# Stm32.net
KiCad netlist of a schematic drawn in Altium Designer
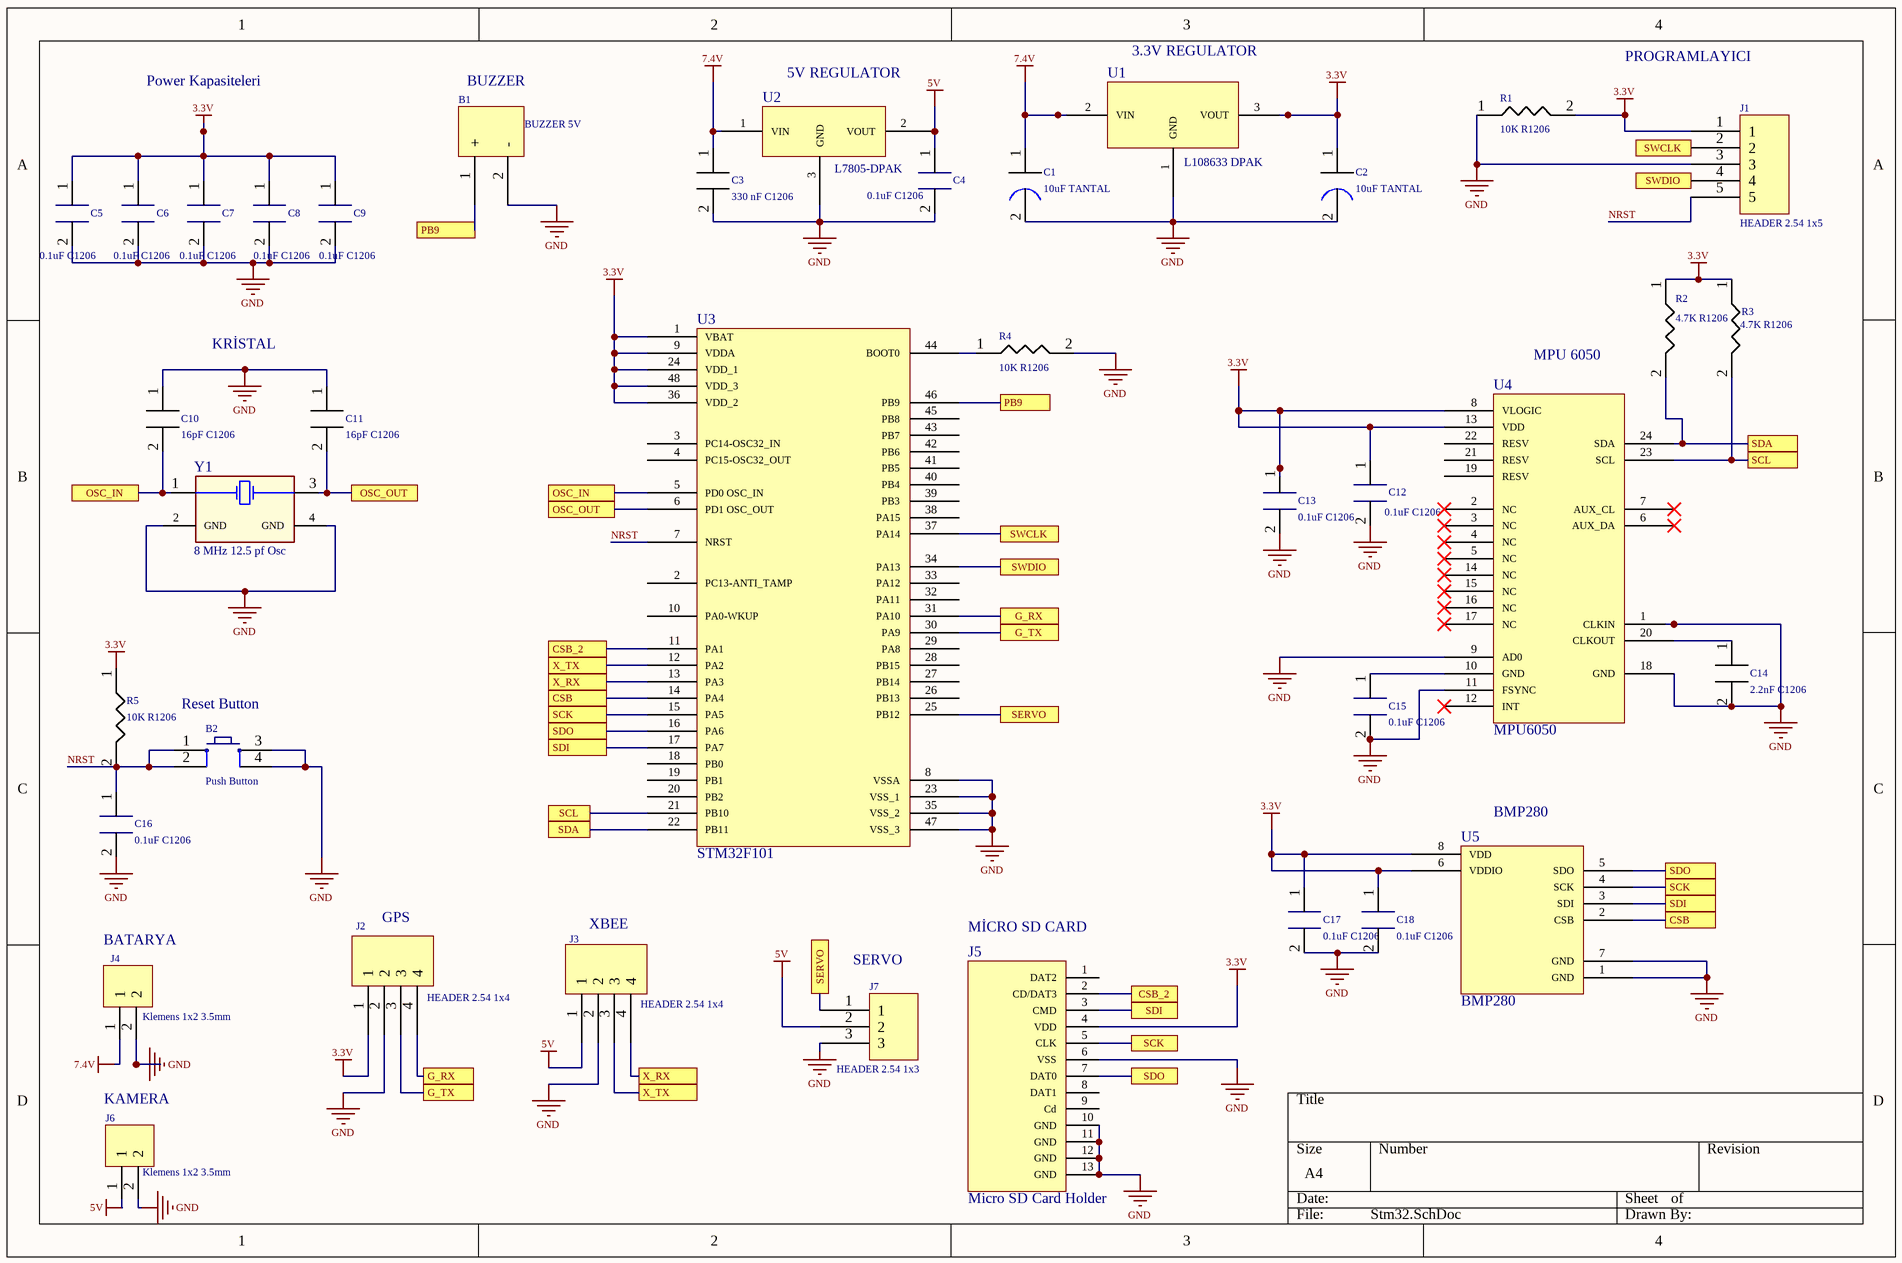
[diagram p0: Stm32.SchDoc]

(export (version "E")
  (design (tool "Eeschema 10.0.6"))
  (components
    (comp (ref "B1")
      (value "BUZZER 5V")
      (footprint "BUZZER 5V")
      (description "BUZZER 5v")
      (libsource (lib "Stm32") (part "BUZZER 5V"))
    )
    (comp (ref "B2")
      (value "Push Button")
      (footprint "PUSB BUTTON-SMD")
      (description "Smd Push Button")
      (libsource (lib "Stm32") (part "Push Button"))
    )
    (comp (ref "C1")
      (value "10uF TANTAL")
      (footprint "C1206- TANTAL")
      (libsource (lib "Stm32") (part "10uF TANTAL"))
    )
    (comp (ref "C2")
      (value "10uF TANTAL")
      (footprint "C1206- TANTAL")
      (libsource (lib "Stm32") (part "10uF TANTAL"))
    )
    (comp (ref "C3")
      (value "330 nF C1206")
      (footprint "C1206")
      (description "330nF C1206")
      (libsource (lib "Stm32") (part "330 nF C1206"))
    )
    (comp (ref "C4") (value "0.1uF C1206") (footprint "C1206") (libsource (lib "Stm32") (part "0.1uF C1206")))
    (comp (ref "C5") (value "0.1uF C1206") (footprint "C1206") (libsource (lib "Stm32") (part "0.1uF C1206")))
    (comp (ref "C6") (value "0.1uF C1206") (footprint "C1206") (libsource (lib "Stm32") (part "0.1uF C1206")))
    (comp (ref "C7") (value "0.1uF C1206") (footprint "C1206") (libsource (lib "Stm32") (part "0.1uF C1206")))
    (comp (ref "C8") (value "0.1uF C1206") (footprint "C1206") (libsource (lib "Stm32") (part "0.1uF C1206")))
    (comp (ref "C9") (value "0.1uF C1206") (footprint "C1206") (libsource (lib "Stm32") (part "0.1uF C1206")))
    (comp (ref "C10") (value "16pF C1206") (footprint "C1206") (libsource (lib "Stm32") (part "16pF C1206")))
    (comp (ref "C11") (value "16pF C1206") (footprint "C1206") (libsource (lib "Stm32") (part "16pF C1206")))
    (comp (ref "C12")
      (value "0.1uF C1206")
      (footprint "C1206")
      (libsource (lib "Stm32") (part "0.1uF C1206"))
    )
    (comp (ref "C13")
      (value "0.1uF C1206")
      (footprint "C1206")
      (libsource (lib "Stm32") (part "0.1uF C1206"))
    )
    (comp (ref "C14")
      (value "2.2nF C1206")
      (footprint "C1206")
      (description "10nF C1206")
      (libsource (lib "Stm32") (part "2.2nF C1206"))
    )
    (comp (ref "C15")
      (value "0.1uF C1206")
      (footprint "C1206")
      (libsource (lib "Stm32") (part "0.1uF C1206"))
    )
    (comp (ref "C16")
      (value "0.1uF C1206")
      (footprint "C1206")
      (libsource (lib "Stm32") (part "0.1uF C1206"))
    )
    (comp (ref "C17")
      (value "0.1uF C1206")
      (footprint "C1206")
      (libsource (lib "Stm32") (part "0.1uF C1206"))
    )
    (comp (ref "C18")
      (value "0.1uF C1206")
      (footprint "C1206")
      (libsource (lib "Stm32") (part "0.1uF C1206"))
    )
    (comp (ref "J1")
      (value "HEADER 2.54 1x5")
      (footprint "HEADER 2.54 1x5")
      (libsource (lib "Stm32") (part "HEADER 2.54 1x5"))
    )
    (comp (ref "J2")
      (value "HEADER 2.54 1x4")
      (footprint "Header 2.54 1x4")
      (libsource (lib "Stm32") (part "HEADER 2.54 1x4"))
    )
    (comp (ref "J3")
      (value "HEADER 2.54 1x4")
      (footprint "Header 2.54 1x4")
      (libsource (lib "Stm32") (part "HEADER 2.54 1x4"))
    )
    (comp (ref "J4")
      (value "Klemens 1x2 3.5mm")
      (footprint "Klemens 1x2 - 3.5mm")
      (libsource (lib "Stm32") (part "Klemens 1x2 3.5mm"))
    )
    (comp (ref "J5")
      (value "Micro SD Card Holder")
      (footprint "Micro SD Kart Holder")
      (libsource (lib "Stm32") (part "Micro SD Card Holder"))
    )
    (comp (ref "J6")
      (value "Klemens 1x2 3.5mm")
      (footprint "Klemens 1x2 - 3.5mm")
      (libsource (lib "Stm32") (part "Klemens 1x2 3.5mm"))
    )
    (comp (ref "J7")
      (value "HEADER 2.54 1x3")
      (footprint "Header 2.54 1x3")
      (libsource (lib "Stm32") (part "HEADER 2.54 1x3"))
    )
    (comp (ref "R1")
      (value "10K R1206")
      (footprint "R1206 Resıstor")
      (libsource (lib "Stm32") (part "10K R1206"))
    )
    (comp (ref "R2")
      (value "4.7K R1206")
      (footprint "R1206 Resıstor")
      (libsource (lib "Stm32") (part "4.7K R1206"))
    )
    (comp (ref "R3")
      (value "4.7K R1206")
      (footprint "R1206 Resıstor")
      (libsource (lib "Stm32") (part "4.7K R1206"))
    )
    (comp (ref "R4")
      (value "10K R1206")
      (footprint "R1206 Resıstor")
      (libsource (lib "Stm32") (part "10K R1206"))
    )
    (comp (ref "R5")
      (value "10K R1206")
      (footprint "R1206 Resıstor")
      (libsource (lib "Stm32") (part "10K R1206"))
    )
    (comp (ref "U1")
      (value "L108633 DPAK")
      (footprint "DPAK228P972X230-3N")
      (description "LD1086 3.3V REGULATOR")
      (libsource (lib "Stm32") (part "L108633 DPAK"))
    )
    (comp (ref "U2")
      (value "L7805-DPAK")
      (footprint "DPAK228P972X230-3N")
      (description "L7805 5V REGULATÖR SMD PAKET")
      (libsource (lib "Stm32") (part "L7805-DPAK"))
    )
    (comp (ref "U3")
      (value "STM32F101")
      (footprint "LQFP48-STM")
      (description "STM32F101 48 PİNLİ MİKROİŞLEMCİ")
      (libsource (lib "Stm32") (part "STM32F101"))
    )
    (comp (ref "U4")
      (value "MPU6050")
      (footprint "QFN50P400X400X90_HS-25N")
      (description "MPU6050 GYRO")
      (libsource (lib "Stm32") (part "MPU6050"))
    )
    (comp (ref "U5")
      (value "BMP280")
      (footprint "BMP280")
      (description "BMP280 SENSOR")
      (libsource (lib "Stm32") (part "BMP280"))
    )
    (comp (ref "Y1")
      (value "8 MHz 12.5 pf Osc")
      (footprint "8 MHZ Osc.")
      (libsource (lib "Stm32") (part "8 MHz 12.5 pf Osc"))
    )
  )
  (nets
    (net (code "1") (name "/CSB") (class "Default")
      (node (ref "U3") (pin "14") (pinfunction "PA4_14") (pintype "passive"))
      (node (ref "U5") (pin "2") (pinfunction "CSB_2") (pintype "passive"))
    )
    (net (code "2") (name "/CSB_2") (class "Default")
      (node (ref "J5") (pin "2") (pinfunction "CD/DAT3_2") (pintype "passive"))
      (node (ref "U3") (pin "11") (pinfunction "PA1_11") (pintype "passive"))
    )
    (net (code "3") (name "/G_RX") (class "Default")
      (node (ref "J2") (pin "4") (pinfunction "4_4") (pintype "passive"))
      (node (ref "U3") (pin "31") (pinfunction "PA10_31") (pintype "passive"))
    )
    (net (code "4") (name "/G_TX") (class "Default")
      (node (ref "J2") (pin "3") (pinfunction "3_3") (pintype "passive"))
      (node (ref "U3") (pin "30") (pinfunction "PA9_30") (pintype "passive"))
    )
    (net (code "5") (name "/NRST") (class "Default")
      (node (ref "B2") (pin "1") (pinfunction "1_1") (pintype "passive"))
      (node (ref "B2") (pin "2") (pinfunction "2_2") (pintype "passive"))
      (node (ref "C16") (pin "1") (pinfunction "1_1") (pintype "passive"))
      (node (ref "J1") (pin "5") (pinfunction "5_5") (pintype "passive"))
      (node (ref "R5") (pin "2") (pinfunction "2_2") (pintype "passive"))
      (node (ref "U3") (pin "7") (pinfunction "NRST_7") (pintype "passive"))
    )
    (net (code "6") (name "/OSC_IN") (class "Default")
      (node (ref "C10") (pin "2") (pinfunction "2_2") (pintype "passive"))
      (node (ref "U3") (pin "5") (pinfunction "PD0_OSC_IN_5") (pintype "passive"))
      (node (ref "Y1") (pin "1") (pintype "power_in"))
    )
    (net (code "7") (name "/OSC_OUT") (class "Default")
      (node (ref "C11") (pin "2") (pinfunction "2_2") (pintype "passive"))
      (node (ref "U3") (pin "6") (pinfunction "PD1_OSC_OUT_6") (pintype "passive"))
      (node (ref "Y1") (pin "3") (pintype "passive"))
    )
    (net (code "8") (name "/PB9") (class "Default")
      (node (ref "B1") (pin "1") (pinfunction "+_1") (pintype "passive"))
      (node (ref "U3") (pin "46") (pinfunction "PB9_46") (pintype "passive"))
    )
    (net (code "9") (name "/SCK") (class "Default")
      (node (ref "J5") (pin "5") (pinfunction "CLK_5") (pintype "passive"))
      (node (ref "U3") (pin "15") (pinfunction "PA5_15") (pintype "passive"))
      (node (ref "U5") (pin "4") (pinfunction "SCK_4") (pintype "passive"))
    )
    (net (code "10") (name "/SCL") (class "Default")
      (node (ref "R3") (pin "2") (pinfunction "2_2") (pintype "passive"))
      (node (ref "U3") (pin "21") (pinfunction "PB10_21") (pintype "passive"))
      (node (ref "U4") (pin "23") (pinfunction "SCL_23") (pintype "passive"))
    )
    (net (code "11") (name "/SDA") (class "Default")
      (node (ref "R2") (pin "2") (pinfunction "2_2") (pintype "passive"))
      (node (ref "U3") (pin "22") (pinfunction "PB11_22") (pintype "passive"))
      (node (ref "U4") (pin "24") (pinfunction "SDA_24") (pintype "passive"))
    )
    (net (code "12") (name "/SDI") (class "Default")
      (node (ref "J5") (pin "3") (pinfunction "CMD_3") (pintype "passive"))
      (node (ref "U3") (pin "17") (pinfunction "PA7_17") (pintype "passive"))
      (node (ref "U5") (pin "3") (pinfunction "SDI_3") (pintype "passive"))
    )
    (net (code "13") (name "/SDO") (class "Default")
      (node (ref "J5") (pin "7") (pinfunction "DAT0_7") (pintype "passive"))
      (node (ref "U3") (pin "16") (pinfunction "PA6_16") (pintype "passive"))
      (node (ref "U5") (pin "5") (pinfunction "SDO_5") (pintype "passive"))
    )
    (net (code "14") (name "/SERVO") (class "Default")
      (node (ref "J7") (pin "1") (pinfunction "1_1") (pintype "passive"))
      (node (ref "U3") (pin "25") (pinfunction "PB12_25") (pintype "passive"))
    )
    (net (code "15") (name "/SWCLK") (class "Default")
      (node (ref "J1") (pin "2") (pinfunction "2_2") (pintype "passive"))
      (node (ref "U3") (pin "37") (pinfunction "PA14_37") (pintype "passive"))
    )
    (net (code "16") (name "/SWDIO") (class "Default")
      (node (ref "J1") (pin "4") (pinfunction "4_4") (pintype "passive"))
      (node (ref "U3") (pin "34") (pinfunction "PA13_34") (pintype "passive"))
    )
    (net (code "17") (name "/X_RX") (class "Default")
      (node (ref "J3") (pin "4") (pinfunction "4_4") (pintype "passive"))
      (node (ref "U3") (pin "13") (pinfunction "PA3_13") (pintype "passive"))
    )
    (net (code "18") (name "/X_TX") (class "Default")
      (node (ref "J3") (pin "3") (pinfunction "3_3") (pintype "passive"))
      (node (ref "U3") (pin "12") (pinfunction "PA2_12") (pintype "passive"))
    )
    (net (code "19") (name "3.3V") (class "Default")
      (node (ref "C12") (pin "1") (pinfunction "1_1") (pintype "passive"))
      (node (ref "C13") (pin "1") (pinfunction "1_1") (pintype "passive"))
      (node (ref "C17") (pin "1") (pinfunction "1_1") (pintype "passive"))
      (node (ref "C18") (pin "1") (pinfunction "1_1") (pintype "passive"))
      (node (ref "C2") (pin "1") (pinfunction "1_1") (pintype "passive"))
      (node (ref "C5") (pin "1") (pinfunction "1_1") (pintype "passive"))
      (node (ref "C6") (pin "1") (pinfunction "1_1") (pintype "passive"))
      (node (ref "C7") (pin "1") (pinfunction "1_1") (pintype "passive"))
      (node (ref "C8") (pin "1") (pinfunction "1_1") (pintype "passive"))
      (node (ref "C9") (pin "1") (pinfunction "1_1") (pintype "passive"))
      (node (ref "J1") (pin "1") (pinfunction "1_1") (pintype "passive"))
      (node (ref "J2") (pin "1") (pinfunction "1_1") (pintype "passive"))
      (node (ref "J5") (pin "4") (pinfunction "VDD_4") (pintype "passive"))
      (node (ref "R1") (pin "2") (pinfunction "2_2") (pintype "passive"))
      (node (ref "R2") (pin "1") (pinfunction "1_1") (pintype "passive"))
      (node (ref "R3") (pin "1") (pinfunction "1_1") (pintype "passive"))
      (node (ref "R5") (pin "1") (pinfunction "1_1") (pintype "passive"))
      (node (ref "U1") (pin "3") (pinfunction "VOUT_3") (pintype "passive"))
      (node (ref "U3") (pin "1") (pinfunction "VBAT_1") (pintype "passive"))
      (node (ref "U3") (pin "24") (pinfunction "VDD_1_24") (pintype "passive"))
      (node (ref "U3") (pin "36") (pinfunction "VDD_2_36") (pintype "passive"))
      (node (ref "U3") (pin "48") (pinfunction "VDD_3_48") (pintype "passive"))
      (node (ref "U3") (pin "9") (pinfunction "VDDA_9") (pintype "passive"))
      (node (ref "U4") (pin "13") (pinfunction "VDD_13") (pintype "passive"))
      (node (ref "U4") (pin "8") (pinfunction "VLOGIC_8") (pintype "passive"))
      (node (ref "U5") (pin "6") (pinfunction "VDDIO_6") (pintype "passive"))
      (node (ref "U5") (pin "8") (pinfunction "VDD_8") (pintype "passive"))
    )
    (net (code "20") (name "5V") (class "Default")
      (node (ref "C4") (pin "1") (pinfunction "1_1") (pintype "passive"))
      (node (ref "J3") (pin "1") (pinfunction "1_1") (pintype "passive"))
      (node (ref "J6") (pin "1") (pinfunction "1_1") (pintype "passive"))
      (node (ref "J7") (pin "2") (pinfunction "2_2") (pintype "passive"))
      (node (ref "U2") (pin "2") (pinfunction "VOUT_2") (pintype "passive"))
    )
    (net (code "21") (name "7.4V") (class "Default")
      (node (ref "C1") (pin "1") (pinfunction "1_1") (pintype "passive"))
      (node (ref "C3") (pin "1") (pinfunction "1_1") (pintype "passive"))
      (node (ref "J4") (pin "1") (pinfunction "1_1") (pintype "passive"))
      (node (ref "U1") (pin "2") (pinfunction "VIN_2") (pintype "passive"))
      (node (ref "U2") (pin "1") (pinfunction "VIN_1") (pintype "passive"))
    )
    (net (code "22") (name "GND") (class "Default")
      (node (ref "B1") (pin "2") (pinfunction "-_2") (pintype "passive"))
      (node (ref "B2") (pin "3") (pinfunction "3_3") (pintype "passive"))
      (node (ref "B2") (pin "4") (pinfunction "4_4") (pintype "passive"))
      (node (ref "C1") (pin "2") (pinfunction "2_2") (pintype "passive"))
      (node (ref "C10") (pin "1") (pinfunction "1_1") (pintype "passive"))
      (node (ref "C11") (pin "1") (pinfunction "1_1") (pintype "passive"))
      (node (ref "C12") (pin "2") (pinfunction "2_2") (pintype "passive"))
      (node (ref "C13") (pin "2") (pinfunction "2_2") (pintype "passive"))
      (node (ref "C14") (pin "2") (pinfunction "2_2") (pintype "passive"))
      (node (ref "C15") (pin "2") (pinfunction "2_2") (pintype "passive"))
      (node (ref "C16") (pin "2") (pinfunction "2_2") (pintype "passive"))
      (node (ref "C17") (pin "2") (pinfunction "2_2") (pintype "passive"))
      (node (ref "C18") (pin "2") (pinfunction "2_2") (pintype "passive"))
      (node (ref "C2") (pin "2") (pinfunction "2_2") (pintype "passive"))
      (node (ref "C3") (pin "2") (pinfunction "2_2") (pintype "passive"))
      (node (ref "C4") (pin "2") (pinfunction "2_2") (pintype "passive"))
      (node (ref "C5") (pin "2") (pinfunction "2_2") (pintype "passive"))
      (node (ref "C6") (pin "2") (pinfunction "2_2") (pintype "passive"))
      (node (ref "C7") (pin "2") (pinfunction "2_2") (pintype "passive"))
      (node (ref "C8") (pin "2") (pinfunction "2_2") (pintype "passive"))
      (node (ref "C9") (pin "2") (pinfunction "2_2") (pintype "passive"))
      (node (ref "J1") (pin "3") (pinfunction "3_3") (pintype "passive"))
      (node (ref "J2") (pin "2") (pinfunction "2_2") (pintype "passive"))
      (node (ref "J3") (pin "2") (pinfunction "2_2") (pintype "passive"))
      (node (ref "J4") (pin "2") (pinfunction "2_2") (pintype "passive"))
      (node (ref "J5") (pin "10") (pinfunction "GND_10") (pintype "passive"))
      (node (ref "J5") (pin "11") (pinfunction "GND_11") (pintype "passive"))
      (node (ref "J5") (pin "12") (pinfunction "GND_12") (pintype "passive"))
      (node (ref "J5") (pin "13") (pinfunction "GND_13") (pintype "passive"))
      (node (ref "J5") (pin "6") (pinfunction "VSS_6") (pintype "passive"))
      (node (ref "J6") (pin "2") (pinfunction "2_2") (pintype "passive"))
      (node (ref "J7") (pin "3") (pinfunction "3_3") (pintype "passive"))
      (node (ref "R1") (pin "1") (pinfunction "1_1") (pintype "passive"))
      (node (ref "R4") (pin "2") (pinfunction "2_2") (pintype "passive"))
      (node (ref "U1") (pin "1") (pinfunction "GND_1") (pintype "passive"))
      (node (ref "U2") (pin "3") (pinfunction "GND_3") (pintype "passive"))
      (node (ref "U3") (pin "23") (pinfunction "VSS_1_23") (pintype "passive"))
      (node (ref "U3") (pin "35") (pinfunction "VSS_2_35") (pintype "passive"))
      (node (ref "U3") (pin "47") (pinfunction "VSS_3_47") (pintype "passive"))
      (node (ref "U3") (pin "8") (pinfunction "VSSA_8") (pintype "passive"))
      (node (ref "U4") (pin "1") (pinfunction "CLKIN_1") (pintype "passive"))
      (node (ref "U4") (pin "11") (pinfunction "FSYNC_11") (pintype "passive"))
      (node (ref "U4") (pin "18") (pinfunction "GND_18") (pintype "passive"))
      (node (ref "U4") (pin "9") (pinfunction "AD0_9") (pintype "passive"))
      (node (ref "U5") (pin "1") (pinfunction "GND_1") (pintype "passive"))
      (node (ref "U5") (pin "7") (pinfunction "GND_7") (pintype "passive"))
      (node (ref "Y1") (pin "2") (pinfunction "GND_2") (pintype "power_in"))
      (node (ref "Y1") (pin "4") (pinfunction "GND_4") (pintype "passive"))
    )
    (net (code "23") (name "Net-(C15-Pad1)") (class "Default")
      (node (ref "C15") (pin "1") (pinfunction "1_1") (pintype "passive"))
      (node (ref "U4") (pin "10") (pinfunction "GND_10") (pintype "passive"))
    )
    (net (code "24") (name "Net-(U3-BOOT0)") (class "Default")
      (node (ref "R4") (pin "1") (pinfunction "1_1") (pintype "passive"))
      (node (ref "U3") (pin "44") (pinfunction "BOOT0_44") (pintype "passive"))
    )
    (net (code "25") (name "Net-(U4-CLKOUT)") (class "Default")
      (node (ref "C14") (pin "1") (pinfunction "1_1") (pintype "passive"))
      (node (ref "U4") (pin "20") (pinfunction "CLKOUT_20") (pintype "passive"))
    )
    (net (code "26") (name "unconnected-(J5-Cd-Pad9)") (class "Default")
      (node (ref "J5") (pin "9") (pinfunction "Cd_9") (pintype "passive"))
    )
    (net (code "27") (name "unconnected-(J5-DAT1-Pad8)") (class "Default")
      (node (ref "J5") (pin "8") (pinfunction "DAT1_8") (pintype "passive"))
    )
    (net (code "28") (name "unconnected-(J5-DAT2-Pad1)") (class "Default")
      (node (ref "J5") (pin "1") (pinfunction "DAT2_1") (pintype "passive"))
    )
    (net (code "29") (name "unconnected-(U3-PA0-WKUP-Pad10)") (class "Default")
      (node (ref "U3") (pin "10") (pinfunction "PA0-WKUP_10") (pintype "passive"))
    )
    (net (code "30") (name "unconnected-(U3-PA8-Pad29)") (class "Default")
      (node (ref "U3") (pin "29") (pinfunction "PA8_29") (pintype "passive"))
    )
    (net (code "31") (name "unconnected-(U3-PA11-Pad32)") (class "Default")
      (node (ref "U3") (pin "32") (pinfunction "PA11_32") (pintype "passive"))
    )
    (net (code "32") (name "unconnected-(U3-PA12-Pad33)") (class "Default")
      (node (ref "U3") (pin "33") (pinfunction "PA12_33") (pintype "passive"))
    )
    (net (code "33") (name "unconnected-(U3-PA15-Pad38)") (class "Default")
      (node (ref "U3") (pin "38") (pinfunction "PA15_38") (pintype "passive"))
    )
    (net (code "34") (name "unconnected-(U3-PB0-Pad18)") (class "Default")
      (node (ref "U3") (pin "18") (pinfunction "PB0_18") (pintype "passive"))
    )
    (net (code "35") (name "unconnected-(U3-PB1-Pad19)") (class "Default")
      (node (ref "U3") (pin "19") (pinfunction "PB1_19") (pintype "passive"))
    )
    (net (code "36") (name "unconnected-(U3-PB2-Pad20)") (class "Default")
      (node (ref "U3") (pin "20") (pinfunction "PB2_20") (pintype "passive"))
    )
    (net (code "37") (name "unconnected-(U3-PB3-Pad39)") (class "Default")
      (node (ref "U3") (pin "39") (pinfunction "PB3_39") (pintype "passive"))
    )
    (net (code "38") (name "unconnected-(U3-PB4-Pad40)") (class "Default")
      (node (ref "U3") (pin "40") (pinfunction "PB4_40") (pintype "passive"))
    )
    (net (code "39") (name "unconnected-(U3-PB5-Pad41)") (class "Default")
      (node (ref "U3") (pin "41") (pinfunction "PB5_41") (pintype "passive"))
    )
    (net (code "40") (name "unconnected-(U3-PB6-Pad42)") (class "Default")
      (node (ref "U3") (pin "42") (pinfunction "PB6_42") (pintype "passive"))
    )
    (net (code "41") (name "unconnected-(U3-PB7-Pad43)") (class "Default")
      (node (ref "U3") (pin "43") (pinfunction "PB7_43") (pintype "passive"))
    )
    (net (code "42") (name "unconnected-(U3-PB8-Pad45)") (class "Default")
      (node (ref "U3") (pin "45") (pinfunction "PB8_45") (pintype "passive"))
    )
    (net (code "43") (name "unconnected-(U3-PB13-Pad26)") (class "Default")
      (node (ref "U3") (pin "26") (pinfunction "PB13_26") (pintype "passive"))
    )
    (net (code "44") (name "unconnected-(U3-PB14-Pad27)") (class "Default")
      (node (ref "U3") (pin "27") (pinfunction "PB14_27") (pintype "passive"))
    )
    (net (code "45") (name "unconnected-(U3-PB15-Pad28)") (class "Default")
      (node (ref "U3") (pin "28") (pinfunction "PB15_28") (pintype "passive"))
    )
    (net (code "46") (name "unconnected-(U3-PC13-ANTI_TAMP-Pad2)") (class "Default")
      (node (ref "U3") (pin "2") (pinfunction "PC13-ANTI_TAMP_2") (pintype "passive"))
    )
    (net (code "47") (name "unconnected-(U3-PC14-OSC32_IN-Pad3)") (class "Default")
      (node (ref "U3") (pin "3") (pinfunction "PC14-OSC32_IN_3") (pintype "passive"))
    )
    (net (code "48") (name "unconnected-(U3-PC15-OSC32_OUT-Pad4)") (class "Default")
      (node (ref "U3") (pin "4") (pinfunction "PC15-OSC32_OUT_4") (pintype "passive"))
    )
    (net (code "49") (name "unconnected-(U4-AUX_CL-Pad7)") (class "Default")
      (node (ref "U4") (pin "7") (pinfunction "AUX_CL_7") (pintype "passive+no_connect"))
    )
    (net (code "50") (name "unconnected-(U4-AUX_DA-Pad6)") (class "Default")
      (node (ref "U4") (pin "6") (pinfunction "AUX_DA_6") (pintype "passive+no_connect"))
    )
    (net (code "51") (name "unconnected-(U4-INT-Pad12)") (class "Default")
      (node (ref "U4") (pin "12") (pinfunction "INT_12") (pintype "passive+no_connect"))
    )
    (net (code "52") (name "unconnected-(U4-NC-Pad2)") (class "Default")
      (node (ref "U4") (pin "2") (pinfunction "NC_2") (pintype "passive+no_connect"))
    )
    (net (code "53") (name "unconnected-(U4-NC-Pad3)") (class "Default")
      (node (ref "U4") (pin "3") (pinfunction "NC_3") (pintype "passive+no_connect"))
    )
    (net (code "54") (name "unconnected-(U4-NC-Pad4)") (class "Default")
      (node (ref "U4") (pin "4") (pinfunction "NC_4") (pintype "passive+no_connect"))
    )
    (net (code "55") (name "unconnected-(U4-NC-Pad5)") (class "Default")
      (node (ref "U4") (pin "5") (pinfunction "NC_5") (pintype "passive+no_connect"))
    )
    (net (code "56") (name "unconnected-(U4-NC-Pad14)") (class "Default")
      (node (ref "U4") (pin "14") (pinfunction "NC_14") (pintype "passive+no_connect"))
    )
    (net (code "57") (name "unconnected-(U4-NC-Pad15)") (class "Default")
      (node (ref "U4") (pin "15") (pinfunction "NC_15") (pintype "passive+no_connect"))
    )
    (net (code "58") (name "unconnected-(U4-NC-Pad16)") (class "Default")
      (node (ref "U4") (pin "16") (pinfunction "NC_16") (pintype "passive+no_connect"))
    )
    (net (code "59") (name "unconnected-(U4-NC-Pad17)") (class "Default")
      (node (ref "U4") (pin "17") (pinfunction "NC_17") (pintype "passive+no_connect"))
    )
    (net (code "60") (name "unconnected-(U4-RESV-Pad19)") (class "Default")
      (node (ref "U4") (pin "19") (pinfunction "RESV_19") (pintype "passive"))
    )
    (net (code "61") (name "unconnected-(U4-RESV-Pad21)") (class "Default")
      (node (ref "U4") (pin "21") (pinfunction "RESV_21") (pintype "passive"))
    )
    (net (code "62") (name "unconnected-(U4-RESV-Pad22)") (class "Default")
      (node (ref "U4") (pin "22") (pinfunction "RESV_22") (pintype "passive"))
    )
  )
)
